# 3_Unextended_Standard_mcu.net
KiCad netlist of a schematic drawn in Altium Designer
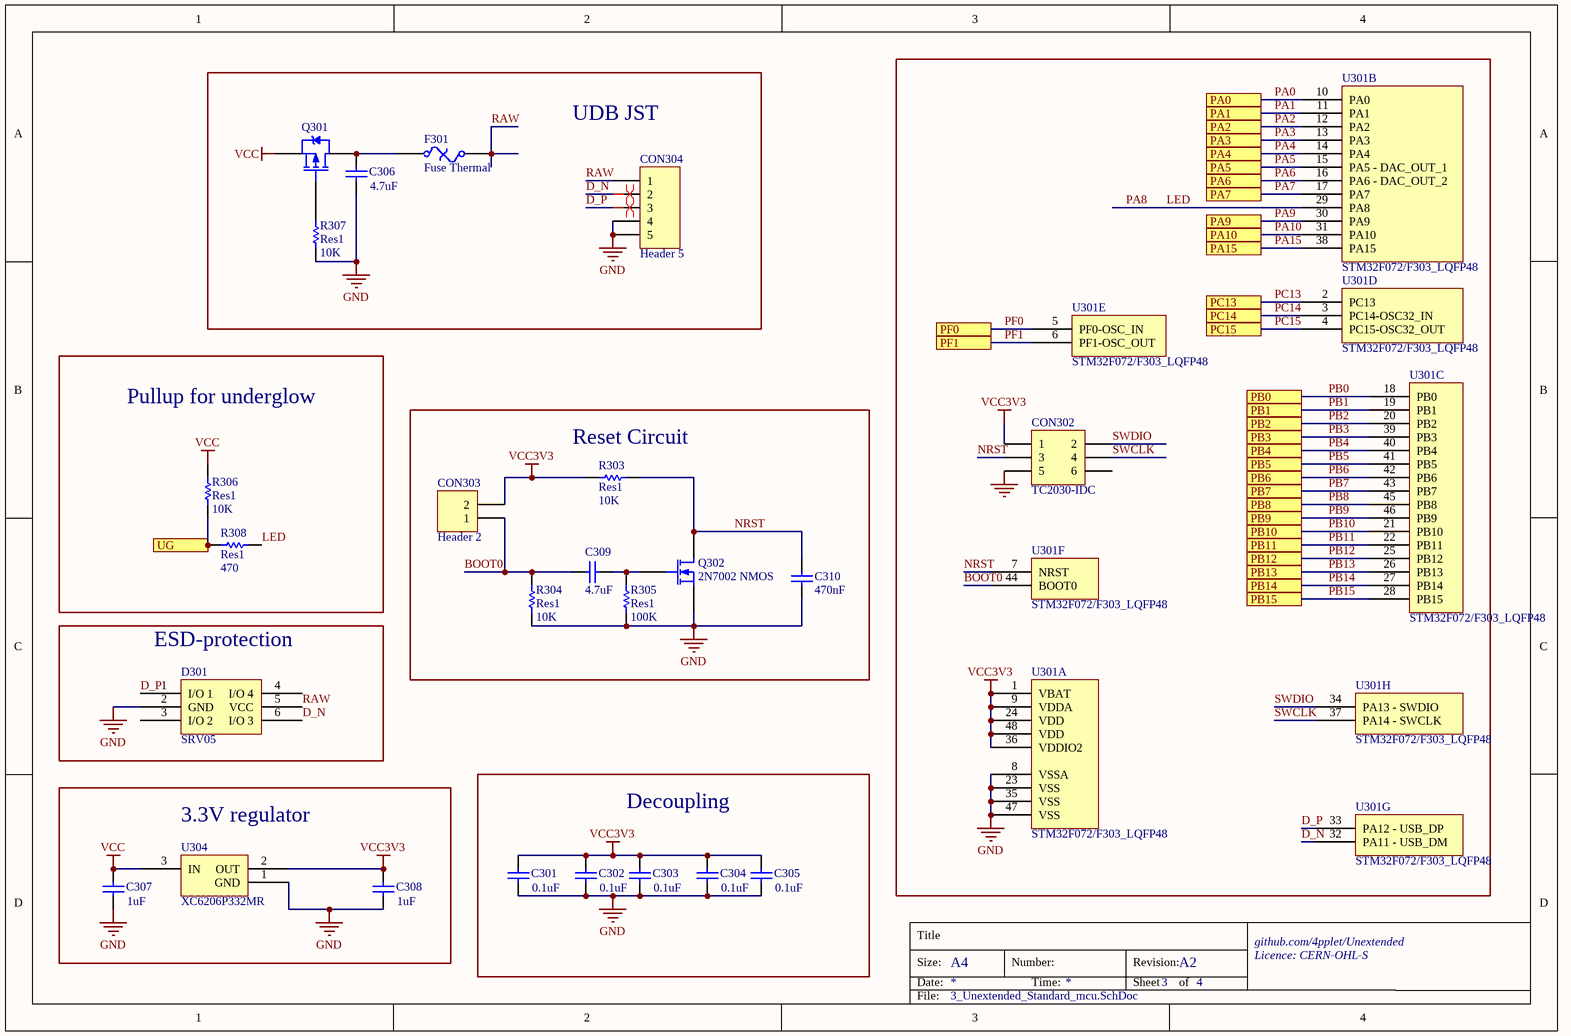
[diagram p0: 3_Unextended_Standard_mcu.SchDoc]

(export (version "E")
  (design (tool "Eeschema 10.0.6"))
  (components
    (comp (ref "C301")
      (value "0.1uF")
      (footprint "C0603[1608]")
      (description "Capacitor")
      (fields (field (name "LCSC PART #") "C14663") (field (name "MRF.PART") "CC0603KRX7R9BB104"))
      (libsource (lib "Miscellaneous Devices") (part "Cap"))
    )
    (comp (ref "C302")
      (value "0.1uF")
      (footprint "C0603[1608]")
      (description "Capacitor")
      (fields (field (name "LCSC PART #") "C14663") (field (name "MRF.PART") "CC0603KRX7R9BB104"))
      (libsource (lib "Miscellaneous Devices") (part "Cap"))
    )
    (comp (ref "C303")
      (value "0.1uF")
      (footprint "C0603[1608]")
      (description "Capacitor")
      (fields (field (name "LCSC PART #") "C14663") (field (name "MRF.PART") "CC0603KRX7R9BB104"))
      (libsource (lib "Miscellaneous Devices") (part "Cap"))
    )
    (comp (ref "C304")
      (value "0.1uF")
      (footprint "C0603[1608]")
      (description "Capacitor")
      (fields (field (name "LCSC PART #") "C14663") (field (name "MRF.PART") "CC0603KRX7R9BB104"))
      (libsource (lib "Miscellaneous Devices") (part "Cap"))
    )
    (comp (ref "C305")
      (value "0.1uF")
      (footprint "C0603[1608]")
      (description "Capacitor")
      (fields (field (name "LCSC PART #") "C14663") (field (name "MRF.PART") "CC0603KRX7R9BB104"))
      (libsource (lib "Miscellaneous Devices") (part "Cap"))
    )
    (comp (ref "C306")
      (value "4.7uF")
      (footprint "C0603[1608]")
      (description "Capacitor")
      (fields (field (name "LCSC PART #") "C19666") (field (name "MRF.PART") "CL10A475KO8NNNC"))
      (libsource (lib "Miscellaneous Devices") (part "Cap"))
    )
    (comp (ref "C307")
      (value "1uF")
      (footprint "C0603[1608]")
      (description "Capacitor")
      (fields (field (name "LCSC PART #") "C15849") (field (name "MRF.PART") "CL10A105KB8NNNC"))
      (libsource (lib "Miscellaneous Devices") (part "Cap"))
    )
    (comp (ref "C308")
      (value "1uF")
      (footprint "C0603[1608]")
      (description "Capacitor")
      (fields (field (name "LCSC PART #") "C15849") (field (name "MRF.PART") "CL10A105KB8NNNC"))
      (libsource (lib "Miscellaneous Devices") (part "Cap"))
    )
    (comp (ref "C309")
      (value "4.7uF")
      (footprint "C0603[1608]")
      (description "Capacitor")
      (fields (field (name "LCSC PART #") "C19666") (field (name "MRF.PART") "CL10A475KO8NNNC"))
      (libsource (lib "Miscellaneous Devices") (part "Cap"))
    )
    (comp (ref "C310")
      (value "470nF")
      (footprint "C0603[1608]")
      (description "Capacitor")
      (fields (field (name "LCSC PART #") "C1623") (field (name "MRF.PART") "CL10B474KA8NNNC"))
      (libsource (lib "Miscellaneous Devices") (part "Cap"))
    )
    (comp (ref "CON302")
      (value "TC2030-IDC")
      (footprint "TC2030-IDC-NL")
      (description "Header, 3-Pin, Dual row")
      (libsource (lib "Miscellaneous Connectors") (part "Header 3X2"))
    )
    (comp (ref "CON303")
      (value "Header 2")
      (footprint "HDR1X2")
      (description "Header, 2-Pin")
      (libsource (lib "Miscellaneous Connectors") (part "Header 2"))
    )
    (comp (ref "CON304")
      (value "Header 5")
      (footprint "JST SM04B-SRSS-TB")
      (description "JST for USB daughter board")
      (fields (field (name "LCSC PART #") "C160404") (field (name "MRF.PART") "SM04B-SRSS-TB(LF)(SN)"))
      (libsource (lib "Miscellaneous Connectors") (part "Header 5"))
    )
    (comp (ref "D301")
      (value "SRV05")
      (footprint "SOT-23-6")
      (fields (field (name "LCSC PART #") "C85364") (field (name "MRF.PART") "SRV05-4-P-T7"))
      (libsource (lib "Keebs") (part "SRV05"))
    )
    (comp (ref "F301")
      (value "Fuse Thermal")
      (footprint "C1206[3216]")
      (description "Thermal Fuse")
      (fields (field (name "LCSC PART #") "C135338") (field (name "MRF.PART") "ASMD1206-050"))
      (libsource (lib "Miscellaneous Devices") (part "Fuse Thermal"))
    )
    (comp (ref "Q301")
      (value "PMOS-2")
      (footprint "SOT-23-3")
      (description "P-Channel Power MOSFET")
      (fields (field (name "LCSC PART #") "C10487") (field (name "MRF.PART") "SI2301CDS-T1-GE3"))
      (libsource (lib "Miscellaneous Devices") (part "PMOS-2"))
    )
    (comp (ref "Q302")
      (value "2N7002 NMOS")
      (footprint "SOT-23-3")
      (description "N-Channel MOSFET")
      (fields (field (name "LCSC PART #") "C8545") (field (name "MRF.PART") "2N7002"))
      (libsource (lib "Miscellaneous Devices") (part "MOSFET-N"))
    )
    (comp (ref "R303")
      (value "Res1")
      (footprint "R0603[1608]")
      (description "Resistor")
      (fields
        (field (name "ALTIUM_VALUE") "10K")
        (field (name "LCSC PART #") "C25804")
        (field (name "MRF.PART") "0603WAF1002T5E")
      )
      (libsource (lib "Miscellaneous Devices") (part "Res1"))
    )
    (comp (ref "R304")
      (value "Res1")
      (footprint "R0603[1608]")
      (description "Resistor")
      (fields
        (field (name "ALTIUM_VALUE") "10K")
        (field (name "LCSC PART #") "C25804")
        (field (name "MRF.PART") "0603WAF1002T5E")
      )
      (libsource (lib "Miscellaneous Devices") (part "Res1"))
    )
    (comp (ref "R305")
      (value "Res1")
      (footprint "R0603[1608]")
      (description "Resistor")
      (fields
        (field (name "ALTIUM_VALUE") "100K")
        (field (name "LCSC PART #") "C25803")
        (field (name "MRF.PART") "0603WAF1003T5E")
      )
      (libsource (lib "Miscellaneous Devices") (part "Res1"))
    )
    (comp (ref "R306")
      (value "Res1")
      (footprint "R0603[1608]")
      (description "Resistor")
      (fields
        (field (name "ALTIUM_VALUE") "10K")
        (field (name "LCSC PART #") "C25804")
        (field (name "MRF.PART") "0603WAF1002T5E")
      )
      (libsource (lib "Miscellaneous Devices") (part "Res1"))
    )
    (comp (ref "R307")
      (value "Res1")
      (footprint "R0603[1608]")
      (description "Resistor")
      (fields
        (field (name "ALTIUM_VALUE") "10K")
        (field (name "LCSC PART #") "C25804")
        (field (name "MRF.PART") "0603WAF1002T5E")
      )
      (libsource (lib "Miscellaneous Devices") (part "Res1"))
    )
    (comp (ref "R308")
      (value "Res1")
      (footprint "R0603[1608]")
      (description "Resistor")
      (fields
        (field (name "ALTIUM_VALUE") "470")
        (field (name "LCSC PART #") "C23179")
        (field (name "MRF.PART") "0603WAF4700T5E")
      )
      (libsource (lib "Miscellaneous Devices") (part "Res1"))
    )
    (comp (ref "U301")
      (value "STM32F072/F303_LQFP48")
      (footprint "STM32 - COMBO 7X7MM")
      (fields (field (name "LCSC PART #") "C915660") (field (name "MRF.PART") "APM32F072CBT6"))
      (libsource (lib "") (part "STM32F072/F303_LQFP48_1"))
    )
    (comp (ref "U304")
      (value "XC6206P332MR")
      (footprint "SOT-23-3")
      (fields (field (name "LCSC PART #") "C5446"))
      (libsource (lib "Keebs") (part "SOT23 LDO"))
    )
  )
  (nets
    (net (code "1") (name "/BOOT0") (class "Default")
      (node (ref "C309") (pin "1") (pinfunction "1_1") (pintype "passive"))
      (node (ref "CON303") (pin "1") (pinfunction "1_1") (pintype "passive"))
      (node (ref "R304") (pin "1") (pinfunction "1_1") (pintype "passive"))
      (node (ref "U301") (pin "44") (pinfunction "BOOT0_44") (pintype "passive"))
    )
    (net (code "2") (name "/D_N") (class "Default")
      (node (ref "CON304") (pin "2") (pinfunction "2_2") (pintype "passive"))
      (node (ref "D301") (pin "6") (pinfunction "I/O_3_6") (pintype "passive"))
      (node (ref "U301") (pin "32") (pinfunction "PA11_-_USB_DM_32") (pintype "passive"))
    )
    (net (code "3") (name "/D_P") (class "Default")
      (node (ref "CON304") (pin "3") (pinfunction "3_3") (pintype "passive"))
      (node (ref "D301") (pin "1") (pinfunction "I/O_1_1") (pintype "passive"))
      (node (ref "U301") (pin "33") (pinfunction "PA12_-_USB_DP_33") (pintype "passive"))
    )
    (net (code "4") (name "/LED") (class "Default")
      (node (ref "R308") (pin "2") (pinfunction "2_2") (pintype "passive"))
      (node (ref "U301") (pin "29") (pinfunction "PA8_29") (pintype "passive"))
    )
    (net (code "5") (name "/NRST") (class "Default")
      (node (ref "C310") (pin "1") (pinfunction "1_1") (pintype "passive"))
      (node (ref "CON302") (pin "3") (pinfunction "3_3") (pintype "passive"))
      (node (ref "Q302") (pin "3") (pinfunction "D_3") (pintype "passive"))
      (node (ref "R303") (pin "2") (pinfunction "2_2") (pintype "passive"))
      (node (ref "U301") (pin "7") (pinfunction "NRST_7") (pintype "passive"))
    )
    (net (code "6") (name "/PA0") (class "Default")
      (node (ref "U301") (pin "10") (pinfunction "PA0_10") (pintype "passive"))
    )
    (net (code "7") (name "/PA1") (class "Default")
      (node (ref "U301") (pin "11") (pinfunction "PA1_11") (pintype "passive"))
    )
    (net (code "8") (name "/PA2") (class "Default")
      (node (ref "U301") (pin "12") (pinfunction "PA2_12") (pintype "passive"))
    )
    (net (code "9") (name "/PA3") (class "Default")
      (node (ref "U301") (pin "13") (pinfunction "PA3_13") (pintype "passive"))
    )
    (net (code "10") (name "/PA4") (class "Default")
      (node (ref "U301") (pin "14") (pinfunction "PA4_14") (pintype "passive"))
    )
    (net (code "11") (name "/PA5") (class "Default")
      (node (ref "U301") (pin "15") (pinfunction "PA5_-_DAC_OUT_1_15") (pintype "passive"))
    )
    (net (code "12") (name "/PA6") (class "Default")
      (node (ref "U301") (pin "16") (pinfunction "PA6_-_DAC_OUT_2_16") (pintype "passive"))
    )
    (net (code "13") (name "/PA7") (class "Default")
      (node (ref "U301") (pin "17") (pinfunction "PA7_17") (pintype "passive"))
    )
    (net (code "14") (name "/PA9") (class "Default")
      (node (ref "U301") (pin "30") (pinfunction "PA9_30") (pintype "passive"))
    )
    (net (code "15") (name "/PA10") (class "Default")
      (node (ref "U301") (pin "31") (pinfunction "PA10_31") (pintype "passive"))
    )
    (net (code "16") (name "/PA15") (class "Default")
      (node (ref "U301") (pin "38") (pinfunction "PA15_38") (pintype "passive"))
    )
    (net (code "17") (name "/PB0") (class "Default")
      (node (ref "U301") (pin "18") (pinfunction "PB0_18") (pintype "passive"))
    )
    (net (code "18") (name "/PB1") (class "Default")
      (node (ref "U301") (pin "19") (pinfunction "PB1_19") (pintype "passive"))
    )
    (net (code "19") (name "/PB2") (class "Default")
      (node (ref "U301") (pin "20") (pinfunction "PB2_20") (pintype "passive"))
    )
    (net (code "20") (name "/PB3") (class "Default")
      (node (ref "U301") (pin "39") (pinfunction "PB3_39") (pintype "passive"))
    )
    (net (code "21") (name "/PB4") (class "Default")
      (node (ref "U301") (pin "40") (pinfunction "PB4_40") (pintype "passive"))
    )
    (net (code "22") (name "/PB5") (class "Default")
      (node (ref "U301") (pin "41") (pinfunction "PB5_41") (pintype "passive"))
    )
    (net (code "23") (name "/PB6") (class "Default")
      (node (ref "U301") (pin "42") (pinfunction "PB6_42") (pintype "passive"))
    )
    (net (code "24") (name "/PB7") (class "Default")
      (node (ref "U301") (pin "43") (pinfunction "PB7_43") (pintype "passive"))
    )
    (net (code "25") (name "/PB8") (class "Default")
      (node (ref "U301") (pin "45") (pinfunction "PB8_45") (pintype "passive"))
    )
    (net (code "26") (name "/PB9") (class "Default")
      (node (ref "U301") (pin "46") (pinfunction "PB9_46") (pintype "passive"))
    )
    (net (code "27") (name "/PB10") (class "Default")
      (node (ref "U301") (pin "21") (pinfunction "PB10_21") (pintype "passive"))
    )
    (net (code "28") (name "/PB11") (class "Default")
      (node (ref "U301") (pin "22") (pinfunction "PB11_22") (pintype "passive"))
    )
    (net (code "29") (name "/PB12") (class "Default")
      (node (ref "U301") (pin "25") (pinfunction "PB12_25") (pintype "passive"))
    )
    (net (code "30") (name "/PB13") (class "Default")
      (node (ref "U301") (pin "26") (pinfunction "PB13_26") (pintype "passive"))
    )
    (net (code "31") (name "/PB14") (class "Default")
      (node (ref "U301") (pin "27") (pinfunction "PB14_27") (pintype "passive"))
    )
    (net (code "32") (name "/PB15") (class "Default")
      (node (ref "U301") (pin "28") (pinfunction "PB15_28") (pintype "passive"))
    )
    (net (code "33") (name "/PC13") (class "Default")
      (node (ref "U301") (pin "2") (pinfunction "PC13_2") (pintype "passive"))
    )
    (net (code "34") (name "/PC14") (class "Default")
      (node (ref "U301") (pin "3") (pinfunction "PC14-OSC32_IN_3") (pintype "passive"))
    )
    (net (code "35") (name "/PC15") (class "Default")
      (node (ref "U301") (pin "4") (pinfunction "PC15-OSC32_OUT_4") (pintype "passive"))
    )
    (net (code "36") (name "/PF0") (class "Default")
      (node (ref "U301") (pin "5") (pinfunction "PF0-OSC_IN_5") (pintype "passive"))
    )
    (net (code "37") (name "/PF1") (class "Default")
      (node (ref "U301") (pin "6") (pinfunction "PF1-OSC_OUT_6") (pintype "passive"))
    )
    (net (code "38") (name "/RAW") (class "Default")
      (node (ref "CON304") (pin "1") (pinfunction "1_1") (pintype "passive"))
      (node (ref "D301") (pin "5") (pinfunction "VCC_5") (pintype "passive"))
      (node (ref "F301") (pin "2") (pinfunction "2_2") (pintype "passive"))
    )
    (net (code "39") (name "/SWCLK") (class "Default")
      (node (ref "CON302") (pin "4") (pinfunction "4_4") (pintype "passive"))
      (node (ref "U301") (pin "37") (pinfunction "PA14_-_SWCLK_37") (pintype "passive"))
    )
    (net (code "40") (name "/SWDIO") (class "Default")
      (node (ref "CON302") (pin "2") (pinfunction "2_2") (pintype "passive"))
      (node (ref "U301") (pin "34") (pinfunction "PA13_-_SWDIO_34") (pintype "passive"))
    )
    (net (code "41") (name "/UG") (class "Default")
      (node (ref "R306") (pin "2") (pinfunction "2_2") (pintype "passive"))
      (node (ref "R308") (pin "1") (pinfunction "1_1") (pintype "passive"))
    )
    (net (code "42") (name "GND") (class "Default")
      (node (ref "C301") (pin "1") (pinfunction "1_1") (pintype "passive"))
      (node (ref "C302") (pin "1") (pinfunction "1_1") (pintype "passive"))
      (node (ref "C303") (pin "1") (pinfunction "1_1") (pintype "passive"))
      (node (ref "C304") (pin "1") (pinfunction "1_1") (pintype "passive"))
      (node (ref "C305") (pin "1") (pinfunction "1_1") (pintype "passive"))
      (node (ref "C306") (pin "1") (pinfunction "1_1") (pintype "passive"))
      (node (ref "C307") (pin "1") (pinfunction "1_1") (pintype "passive"))
      (node (ref "C308") (pin "1") (pinfunction "1_1") (pintype "passive"))
      (node (ref "C310") (pin "2") (pinfunction "2_2") (pintype "passive"))
      (node (ref "CON302") (pin "5") (pinfunction "5_5") (pintype "passive"))
      (node (ref "CON304") (pin "4") (pinfunction "4_4") (pintype "passive"))
      (node (ref "CON304") (pin "5") (pinfunction "5_5") (pintype "passive"))
      (node (ref "D301") (pin "2") (pinfunction "GND_2") (pintype "passive"))
      (node (ref "Q302") (pin "2") (pinfunction "S_2") (pintype "passive"))
      (node (ref "R304") (pin "2") (pinfunction "2_2") (pintype "passive"))
      (node (ref "R305") (pin "2") (pinfunction "2_2") (pintype "passive"))
      (node (ref "R307") (pin "2") (pinfunction "2_2") (pintype "passive"))
      (node (ref "U301") (pin "23") (pinfunction "VSS_23") (pintype "passive"))
      (node (ref "U301") (pin "35") (pinfunction "VSS_35") (pintype "passive"))
      (node (ref "U301") (pin "47") (pinfunction "VSS_47") (pintype "passive"))
      (node (ref "U301") (pin "8") (pinfunction "VSSA_8") (pintype "passive"))
      (node (ref "U304") (pin "1") (pinfunction "GND_1") (pintype "passive"))
    )
    (net (code "43") (name "Net-(Q301-D)") (class "Default")
      (node (ref "C306") (pin "2") (pinfunction "2_2") (pintype "passive"))
      (node (ref "F301") (pin "1") (pinfunction "1_1") (pintype "passive"))
      (node (ref "Q301") (pin "3") (pinfunction "D_3") (pintype "passive"))
    )
    (net (code "44") (name "Net-(Q301-G)") (class "Default")
      (node (ref "Q301") (pin "1") (pinfunction "G_1") (pintype "passive"))
      (node (ref "R307") (pin "1") (pinfunction "1_1") (pintype "passive"))
    )
    (net (code "45") (name "Net-(Q302-G)") (class "Default")
      (node (ref "C309") (pin "2") (pinfunction "2_2") (pintype "passive"))
      (node (ref "Q302") (pin "1") (pinfunction "G_1") (pintype "passive"))
      (node (ref "R305") (pin "1") (pinfunction "1_1") (pintype "passive"))
    )
    (net (code "46") (name "VCC") (class "Default")
      (node (ref "C307") (pin "2") (pinfunction "2_2") (pintype "passive"))
      (node (ref "Q301") (pin "2") (pinfunction "S_2") (pintype "passive"))
      (node (ref "R306") (pin "1") (pinfunction "1_1") (pintype "passive"))
      (node (ref "U304") (pin "3") (pinfunction "IN_3") (pintype "passive"))
    )
    (net (code "47") (name "VCC3V3") (class "Default")
      (node (ref "C301") (pin "2") (pinfunction "2_2") (pintype "passive"))
      (node (ref "C302") (pin "2") (pinfunction "2_2") (pintype "passive"))
      (node (ref "C303") (pin "2") (pinfunction "2_2") (pintype "passive"))
      (node (ref "C304") (pin "2") (pinfunction "2_2") (pintype "passive"))
      (node (ref "C305") (pin "2") (pinfunction "2_2") (pintype "passive"))
      (node (ref "C308") (pin "2") (pinfunction "2_2") (pintype "passive"))
      (node (ref "CON302") (pin "1") (pinfunction "1_1") (pintype "passive"))
      (node (ref "CON303") (pin "2") (pinfunction "2_2") (pintype "passive"))
      (node (ref "R303") (pin "1") (pinfunction "1_1") (pintype "passive"))
      (node (ref "U301") (pin "1") (pinfunction "VBAT_1") (pintype "passive"))
      (node (ref "U301") (pin "24") (pinfunction "VDD_24") (pintype "passive"))
      (node (ref "U301") (pin "36") (pinfunction "VDDIO2_36") (pintype "passive"))
      (node (ref "U301") (pin "48") (pinfunction "VDD_48") (pintype "passive"))
      (node (ref "U301") (pin "9") (pinfunction "VDDA_9") (pintype "passive"))
      (node (ref "U304") (pin "2") (pinfunction "OUT_2") (pintype "passive"))
    )
    (net (code "48") (name "unconnected-(CON302-Pad6)") (class "Default")
      (node (ref "CON302") (pin "6") (pinfunction "6_6") (pintype "passive"))
    )
    (net (code "49") (name "unconnected-(D301-I{slash}O_2-Pad3)") (class "Default")
      (node (ref "D301") (pin "3") (pinfunction "I/O_2_3") (pintype "passive"))
    )
    (net (code "50") (name "unconnected-(D301-I{slash}O_4-Pad4)") (class "Default")
      (node (ref "D301") (pin "4") (pinfunction "I/O_4_4") (pintype "passive"))
    )
  )
)
